# SCH_2023_-_Masters_Project_2023-11-29.net
KiCad netlist of a schematic drawn in EasyEDA
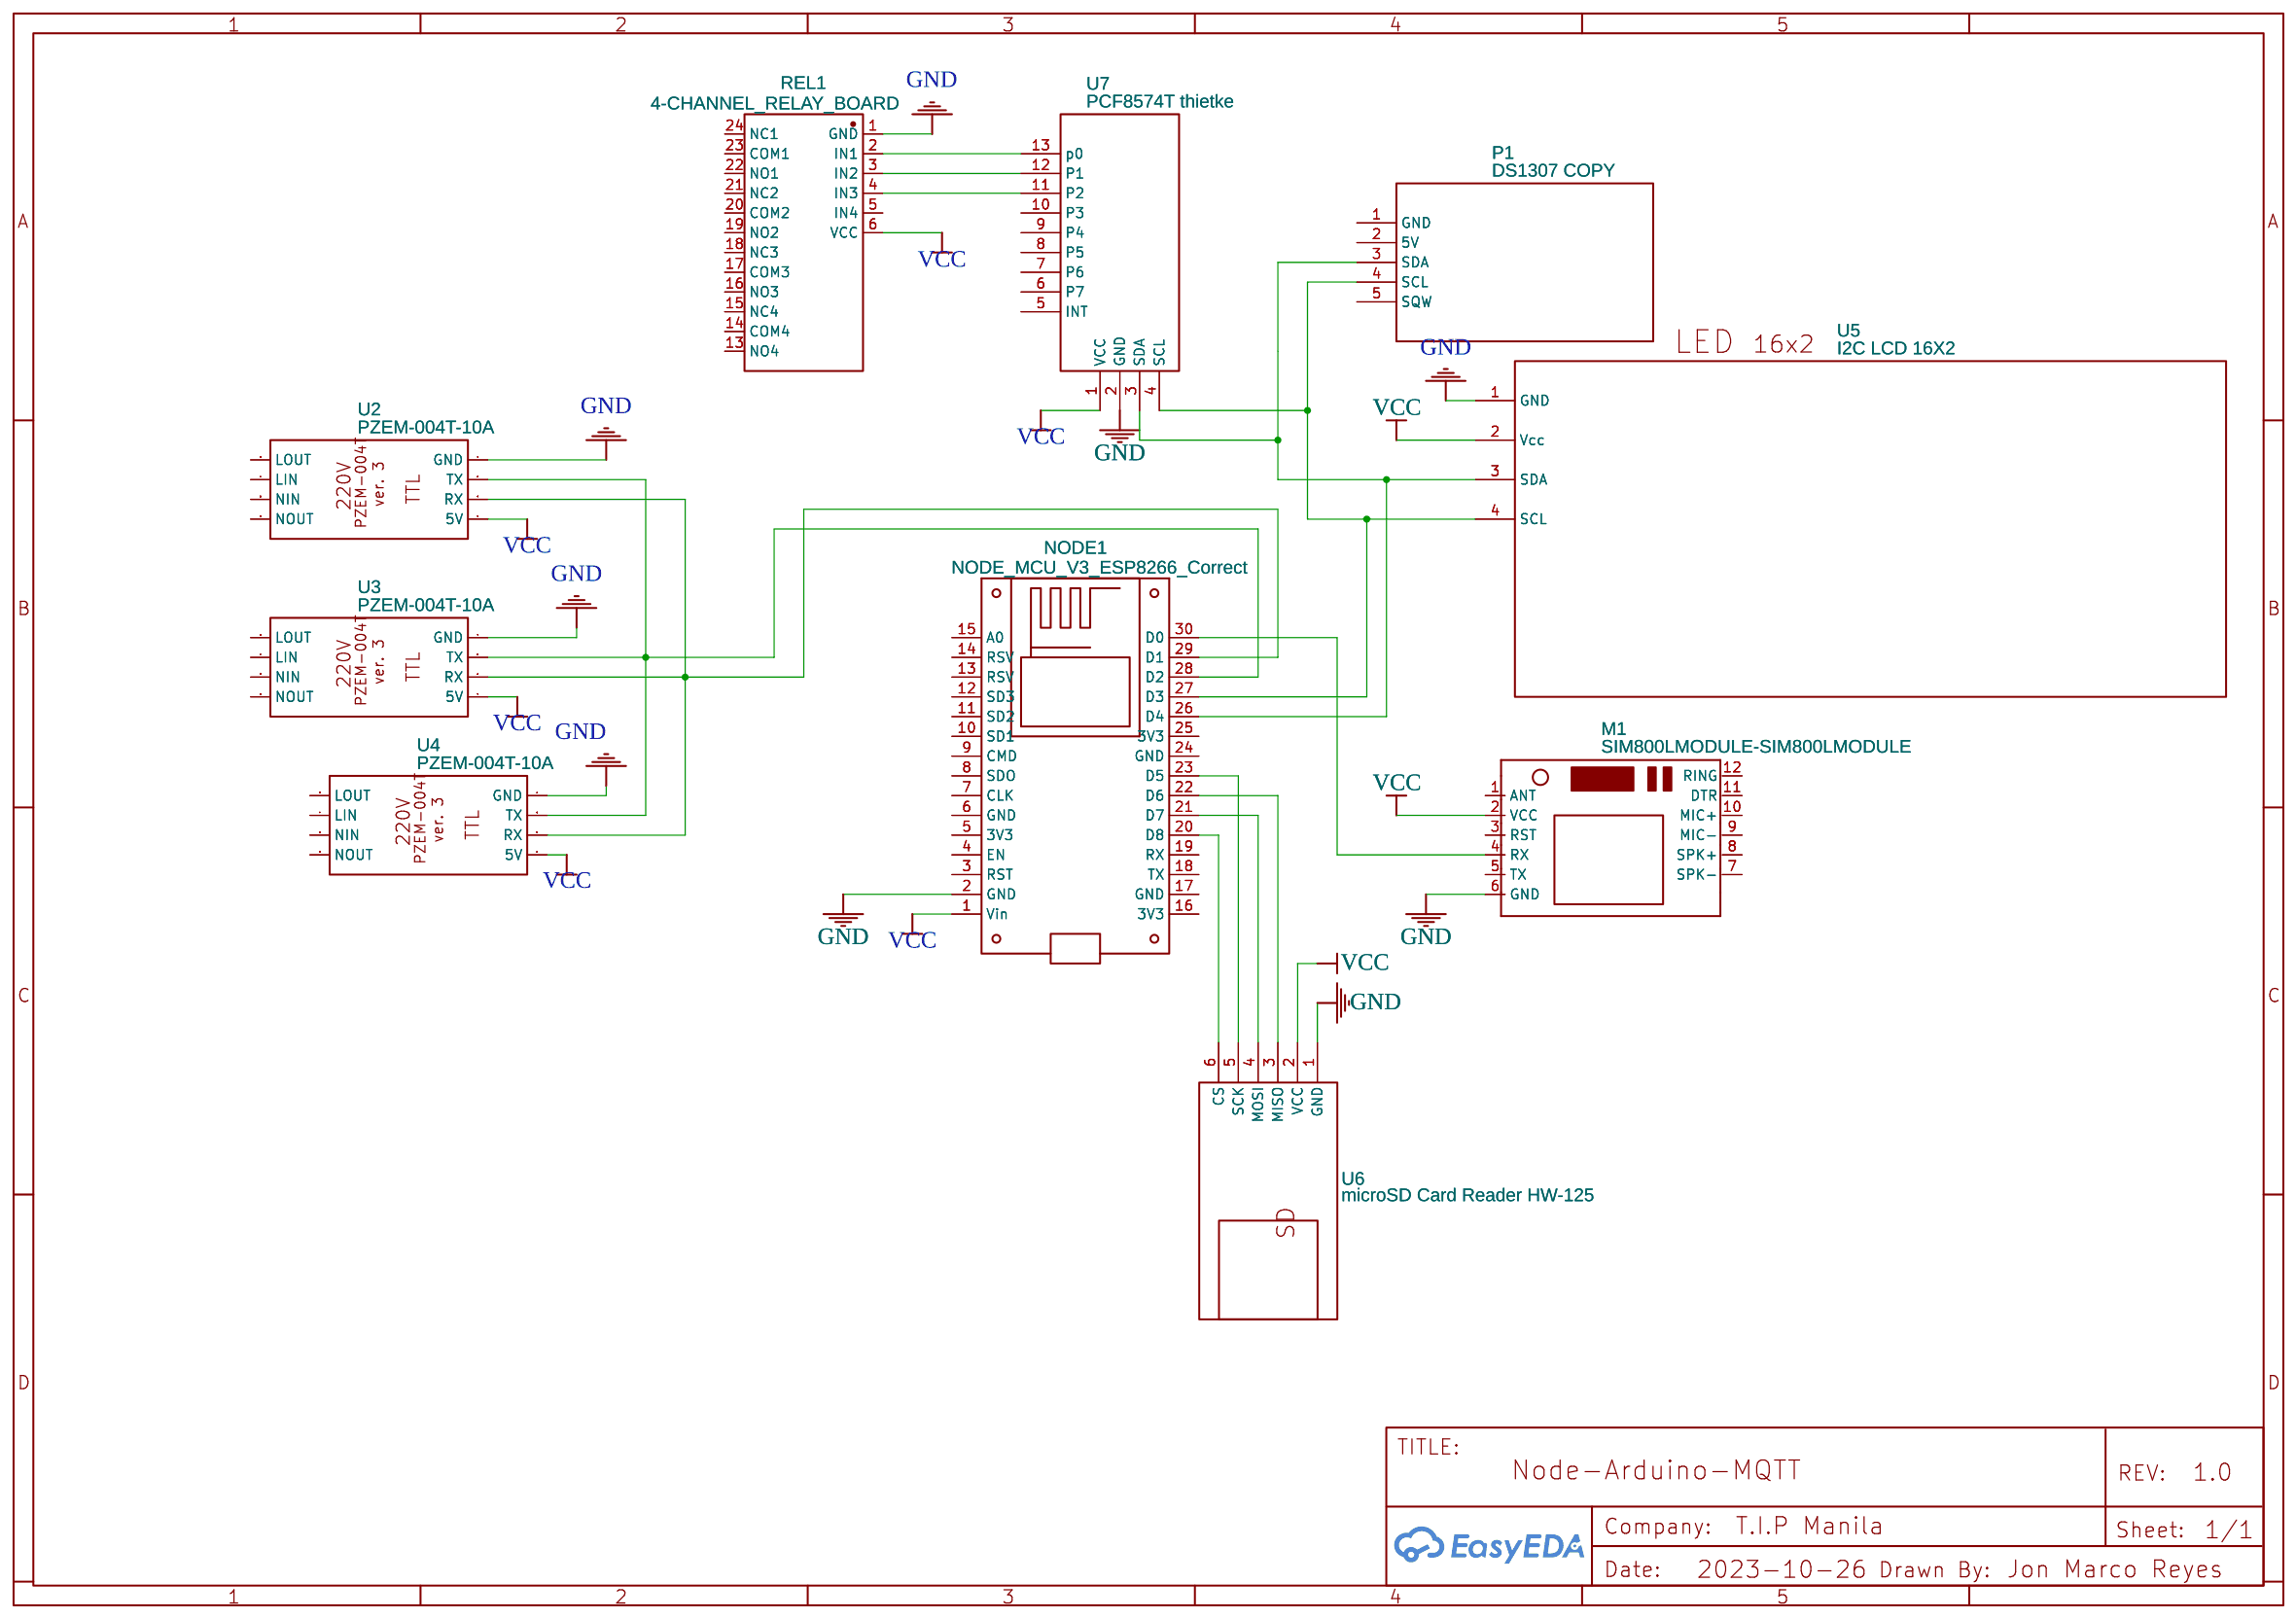
[diagram p0: schematic sheet]

(export (version "E")
  (design (tool "Eeschema 10.0.6"))
  (components
    (comp (ref "M1")
      (value "SIM800LMODULE-SIM800LMODULE")
      (libsource (lib "") (part "SIM800LMODULE-SIM800LMODULE"))
    )
    (comp (ref "NODE1")
      (value "NODE_MCU_V3_ESP8266_Correct")
      (libsource (lib "") (part "NODE_MCU_V3_ESP8266_Correct"))
    )
    (comp (ref "P1") (value "DS1307 COPY") (libsource (lib "") (part "DS1307 COPY")))
    (comp (ref "REL1") (value "4-CHANNEL_RELAY_BOARD") (libsource (lib "") (part "4-CHANNEL_RELAY_BOARD")))
    (comp (ref "U2") (value "PZEM-004T-10A") (libsource (lib "") (part "PZEM-004T-10A")))
    (comp (ref "U3") (value "PZEM-004T-10A") (libsource (lib "") (part "PZEM-004T-10A")))
    (comp (ref "U4") (value "PZEM-004T-10A") (libsource (lib "") (part "PZEM-004T-10A")))
    (comp (ref "U5") (value "I2C LCD 16X2") (libsource (lib "") (part "I2C LCD 16X2")))
    (comp (ref "U6")
      (value "microSD Card Reader HW-125")
      (libsource (lib "") (part "microSD Card Reader HW-125"))
    )
    (comp (ref "U7") (value "PCF8574T thietke") (libsource (lib "") (part "PCF8574T thietke")))
  )
  (nets
    (net (code "1") (name "GND") (class "Default")
      (node (ref "M1") (pin "6") (pinfunction "GND_6") (pintype "output"))
      (node (ref "NODE1") (pin "2") (pinfunction "GND_2") (pintype "unspecified"))
      (node (ref "REL1") (pin "1") (pinfunction "GND_1") (pintype "unspecified"))
      (node (ref "U2") (pin "4") (pinfunction "GND_4") (pintype "unspecified"))
      (node (ref "U3") (pin "4") (pinfunction "GND_4") (pintype "unspecified"))
      (node (ref "U4") (pin "4") (pinfunction "GND_4") (pintype "unspecified"))
      (node (ref "U5") (pin "1") (pinfunction "GND_1") (pintype "unspecified"))
      (node (ref "U6") (pin "1") (pinfunction "GND_1") (pintype "unspecified"))
      (node (ref "U7") (pin "2") (pinfunction "GND_2") (pintype "unspecified"))
    )
    (net (code "2") (name "Net-(M1-RX)") (class "Default")
      (node (ref "M1") (pin "4") (pinfunction "RX_4") (pintype "input"))
      (node (ref "NODE1") (pin "30") (pinfunction "D0_30") (pintype "unspecified"))
    )
    (net (code "3") (name "Net-(NODE1-D1)") (class "Default")
      (node (ref "NODE1") (pin "29") (pinfunction "D1_29") (pintype "unspecified"))
      (node (ref "U2") (pin "2") (pinfunction "RX_2") (pintype "unspecified"))
      (node (ref "U3") (pin "2") (pinfunction "RX_2") (pintype "unspecified"))
      (node (ref "U4") (pin "2") (pinfunction "RX_2") (pintype "unspecified"))
    )
    (net (code "4") (name "Net-(NODE1-D2)") (class "Default")
      (node (ref "NODE1") (pin "28") (pinfunction "D2_28") (pintype "unspecified"))
      (node (ref "U2") (pin "3") (pinfunction "TX_3") (pintype "unspecified"))
      (node (ref "U3") (pin "3") (pinfunction "TX_3") (pintype "unspecified"))
      (node (ref "U4") (pin "3") (pinfunction "TX_3") (pintype "unspecified"))
    )
    (net (code "5") (name "Net-(NODE1-D3)") (class "Default")
      (node (ref "NODE1") (pin "27") (pinfunction "D3_27") (pintype "unspecified"))
      (node (ref "P1") (pin "4") (pinfunction "SCL_4") (pintype "unspecified"))
      (node (ref "U5") (pin "4") (pinfunction "SCL_4") (pintype "unspecified"))
      (node (ref "U7") (pin "4") (pinfunction "SCL_4") (pintype "unspecified"))
    )
    (net (code "6") (name "Net-(NODE1-D4)") (class "Default")
      (node (ref "NODE1") (pin "26") (pinfunction "D4_26") (pintype "unspecified"))
      (node (ref "P1") (pin "3") (pinfunction "SDA_3") (pintype "unspecified"))
      (node (ref "U5") (pin "3") (pinfunction "SDA_3") (pintype "unspecified"))
      (node (ref "U7") (pin "3") (pinfunction "SDA_3") (pintype "unspecified"))
    )
    (net (code "7") (name "Net-(NODE1-D5)") (class "Default")
      (node (ref "NODE1") (pin "23") (pinfunction "D5_23") (pintype "unspecified"))
      (node (ref "U6") (pin "5") (pinfunction "SCK_5") (pintype "unspecified"))
    )
    (net (code "8") (name "Net-(NODE1-D6)") (class "Default")
      (node (ref "NODE1") (pin "22") (pinfunction "D6_22") (pintype "unspecified"))
      (node (ref "U6") (pin "3") (pinfunction "MISO_3") (pintype "unspecified"))
    )
    (net (code "9") (name "Net-(NODE1-D7)") (class "Default")
      (node (ref "NODE1") (pin "21") (pinfunction "D7_21") (pintype "unspecified"))
      (node (ref "U6") (pin "4") (pinfunction "MOSI_4") (pintype "unspecified"))
    )
    (net (code "10") (name "Net-(NODE1-D8)") (class "Default")
      (node (ref "NODE1") (pin "20") (pinfunction "D8_20") (pintype "unspecified"))
      (node (ref "U6") (pin "6") (pinfunction "CS_6") (pintype "unspecified"))
    )
    (net (code "11") (name "Net-(REL1-IN1)") (class "Default")
      (node (ref "REL1") (pin "2") (pinfunction "IN1_2") (pintype "unspecified"))
      (node (ref "U7") (pin "13") (pinfunction "p0_13") (pintype "unspecified"))
    )
    (net (code "12") (name "Net-(REL1-IN2)") (class "Default")
      (node (ref "REL1") (pin "3") (pinfunction "IN2_3") (pintype "unspecified"))
      (node (ref "U7") (pin "12") (pinfunction "P1_12") (pintype "unspecified"))
    )
    (net (code "13") (name "Net-(REL1-IN3)") (class "Default")
      (node (ref "REL1") (pin "4") (pinfunction "IN3_4") (pintype "unspecified"))
      (node (ref "U7") (pin "11") (pinfunction "P2_11") (pintype "unspecified"))
    )
    (net (code "14") (name "VCC") (class "Default")
      (node (ref "M1") (pin "2") (pinfunction "VCC_2") (pintype "input"))
      (node (ref "NODE1") (pin "1") (pinfunction "Vin_1") (pintype "unspecified"))
      (node (ref "REL1") (pin "6") (pinfunction "VCC_6") (pintype "unspecified"))
      (node (ref "U2") (pin "1") (pinfunction "5V_1") (pintype "unspecified"))
      (node (ref "U3") (pin "1") (pinfunction "5V_1") (pintype "unspecified"))
      (node (ref "U4") (pin "1") (pinfunction "5V_1") (pintype "unspecified"))
      (node (ref "U5") (pin "2") (pinfunction "Vcc_2") (pintype "unspecified"))
      (node (ref "U6") (pin "2") (pinfunction "VCC_2") (pintype "unspecified"))
      (node (ref "U7") (pin "1") (pinfunction "VCC_1") (pintype "unspecified"))
    )
    (net (code "15") (name "unconnected-(M1-ANT-Pad1)") (class "Default")
      (node (ref "M1") (pin "1") (pinfunction "ANT_1") (pintype "output"))
    )
    (net (code "16") (name "unconnected-(M1-DTR-Pad11)") (class "Default")
      (node (ref "M1") (pin "11") (pinfunction "DTR_11") (pintype "output"))
    )
    (net (code "17") (name "unconnected-(M1-MIC+-Pad10)") (class "Default")
      (node (ref "M1") (pin "10") (pinfunction "MIC+_10") (pintype "input"))
    )
    (net (code "18") (name "unconnected-(M1-MIC--Pad9)") (class "Default")
      (node (ref "M1") (pin "9") (pinfunction "MIC-_9") (pintype "input"))
    )
    (net (code "19") (name "unconnected-(M1-RING-Pad12)") (class "Default")
      (node (ref "M1") (pin "12") (pinfunction "RING_12") (pintype "output"))
    )
    (net (code "20") (name "unconnected-(M1-RST-Pad3)") (class "Default")
      (node (ref "M1") (pin "3") (pinfunction "RST_3") (pintype "input"))
    )
    (net (code "21") (name "unconnected-(M1-SPK+-Pad8)") (class "Default")
      (node (ref "M1") (pin "8") (pinfunction "SPK+_8") (pintype "output"))
    )
    (net (code "22") (name "unconnected-(M1-SPK--Pad7)") (class "Default")
      (node (ref "M1") (pin "7") (pinfunction "SPK-_7") (pintype "output"))
    )
    (net (code "23") (name "unconnected-(M1-TX-Pad5)") (class "Default")
      (node (ref "M1") (pin "5") (pinfunction "TX_5") (pintype "output"))
    )
    (net (code "24") (name "unconnected-(NODE1-3V3-Pad5)") (class "Default")
      (node (ref "NODE1") (pin "5") (pinfunction "3V3_5") (pintype "unspecified"))
    )
    (net (code "25") (name "unconnected-(NODE1-3V3-Pad16)") (class "Default")
      (node (ref "NODE1") (pin "16") (pinfunction "3V3_16") (pintype "unspecified"))
    )
    (net (code "26") (name "unconnected-(NODE1-3V3-Pad25)") (class "Default")
      (node (ref "NODE1") (pin "25") (pinfunction "3V3_25") (pintype "unspecified"))
    )
    (net (code "27") (name "unconnected-(NODE1-A0-Pad15)") (class "Default")
      (node (ref "NODE1") (pin "15") (pinfunction "A0_15") (pintype "unspecified"))
    )
    (net (code "28") (name "unconnected-(NODE1-CLK-Pad7)") (class "Default")
      (node (ref "NODE1") (pin "7") (pinfunction "CLK_7") (pintype "unspecified"))
    )
    (net (code "29") (name "unconnected-(NODE1-CMD-Pad9)") (class "Default")
      (node (ref "NODE1") (pin "9") (pinfunction "CMD_9") (pintype "unspecified"))
    )
    (net (code "30") (name "unconnected-(NODE1-EN-Pad4)") (class "Default")
      (node (ref "NODE1") (pin "4") (pinfunction "EN_4") (pintype "unspecified"))
    )
    (net (code "31") (name "unconnected-(NODE1-GND-Pad6)") (class "Default")
      (node (ref "NODE1") (pin "6") (pinfunction "GND_6") (pintype "unspecified"))
    )
    (net (code "32") (name "unconnected-(NODE1-GND-Pad17)") (class "Default")
      (node (ref "NODE1") (pin "17") (pinfunction "GND_17") (pintype "unspecified"))
    )
    (net (code "33") (name "unconnected-(NODE1-GND-Pad24)") (class "Default")
      (node (ref "NODE1") (pin "24") (pinfunction "GND_24") (pintype "unspecified"))
    )
    (net (code "34") (name "unconnected-(NODE1-RST-Pad3)") (class "Default")
      (node (ref "NODE1") (pin "3") (pinfunction "RST_3") (pintype "unspecified"))
    )
    (net (code "35") (name "unconnected-(NODE1-RSV-Pad13)") (class "Default")
      (node (ref "NODE1") (pin "13") (pinfunction "RSV_13") (pintype "unspecified"))
    )
    (net (code "36") (name "unconnected-(NODE1-RSV-Pad14)") (class "Default")
      (node (ref "NODE1") (pin "14") (pinfunction "RSV_14") (pintype "unspecified"))
    )
    (net (code "37") (name "unconnected-(NODE1-RX-Pad19)") (class "Default")
      (node (ref "NODE1") (pin "19") (pinfunction "RX_19") (pintype "unspecified"))
    )
    (net (code "38") (name "unconnected-(NODE1-SD1-Pad10)") (class "Default")
      (node (ref "NODE1") (pin "10") (pinfunction "SD1_10") (pintype "unspecified"))
    )
    (net (code "39") (name "unconnected-(NODE1-SD2-Pad11)") (class "Default")
      (node (ref "NODE1") (pin "11") (pinfunction "SD2_11") (pintype "unspecified"))
    )
    (net (code "40") (name "unconnected-(NODE1-SD3-Pad12)") (class "Default")
      (node (ref "NODE1") (pin "12") (pinfunction "SD3_12") (pintype "unspecified"))
    )
    (net (code "41") (name "unconnected-(NODE1-SDO-Pad8)") (class "Default")
      (node (ref "NODE1") (pin "8") (pinfunction "SDO_8") (pintype "unspecified"))
    )
    (net (code "42") (name "unconnected-(NODE1-TX-Pad18)") (class "Default")
      (node (ref "NODE1") (pin "18") (pinfunction "TX_18") (pintype "unspecified"))
    )
    (net (code "43") (name "unconnected-(P1-5V-Pad2)") (class "Default")
      (node (ref "P1") (pin "2") (pinfunction "5V_2") (pintype "unspecified"))
    )
    (net (code "44") (name "unconnected-(P1-GND-Pad1)") (class "Default")
      (node (ref "P1") (pin "1") (pinfunction "GND_1") (pintype "unspecified"))
    )
    (net (code "45") (name "unconnected-(P1-SQW-Pad5)") (class "Default")
      (node (ref "P1") (pin "5") (pinfunction "SQW_5") (pintype "unspecified"))
    )
    (net (code "46") (name "unconnected-(REL1-COM1-Pad23)") (class "Default")
      (node (ref "REL1") (pin "23") (pinfunction "COM1_23") (pintype "unspecified"))
    )
    (net (code "47") (name "unconnected-(REL1-COM2-Pad20)") (class "Default")
      (node (ref "REL1") (pin "20") (pinfunction "COM2_20") (pintype "unspecified"))
    )
    (net (code "48") (name "unconnected-(REL1-COM3-Pad17)") (class "Default")
      (node (ref "REL1") (pin "17") (pinfunction "COM3_17") (pintype "unspecified"))
    )
    (net (code "49") (name "unconnected-(REL1-COM4-Pad14)") (class "Default")
      (node (ref "REL1") (pin "14") (pinfunction "COM4_14") (pintype "unspecified"))
    )
    (net (code "50") (name "unconnected-(REL1-IN4-Pad5)") (class "Default")
      (node (ref "REL1") (pin "5") (pinfunction "IN4_5") (pintype "unspecified"))
    )
    (net (code "51") (name "unconnected-(REL1-NC1-Pad24)") (class "Default")
      (node (ref "REL1") (pin "24") (pinfunction "NC1_24") (pintype "unspecified"))
    )
    (net (code "52") (name "unconnected-(REL1-NC2-Pad21)") (class "Default")
      (node (ref "REL1") (pin "21") (pinfunction "NC2_21") (pintype "unspecified"))
    )
    (net (code "53") (name "unconnected-(REL1-NC3-Pad18)") (class "Default")
      (node (ref "REL1") (pin "18") (pinfunction "NC3_18") (pintype "unspecified"))
    )
    (net (code "54") (name "unconnected-(REL1-NC4-Pad15)") (class "Default")
      (node (ref "REL1") (pin "15") (pinfunction "NC4_15") (pintype "unspecified"))
    )
    (net (code "55") (name "unconnected-(REL1-NO1-Pad22)") (class "Default")
      (node (ref "REL1") (pin "22") (pinfunction "NO1_22") (pintype "unspecified"))
    )
    (net (code "56") (name "unconnected-(REL1-NO2-Pad19)") (class "Default")
      (node (ref "REL1") (pin "19") (pinfunction "NO2_19") (pintype "unspecified"))
    )
    (net (code "57") (name "unconnected-(REL1-NO3-Pad16)") (class "Default")
      (node (ref "REL1") (pin "16") (pinfunction "NO3_16") (pintype "unspecified"))
    )
    (net (code "58") (name "unconnected-(REL1-NO4-Pad13)") (class "Default")
      (node (ref "REL1") (pin "13") (pinfunction "NO4_13") (pintype "unspecified"))
    )
    (net (code "59") (name "unconnected-(U2-LIN-Pad7)") (class "Default")
      (node (ref "U2") (pin "7") (pinfunction "LIN_7") (pintype "unspecified"))
    )
    (net (code "60") (name "unconnected-(U2-LOUT-Pad8)") (class "Default")
      (node (ref "U2") (pin "8") (pinfunction "LOUT_8") (pintype "unspecified"))
    )
    (net (code "61") (name "unconnected-(U2-NIN-Pad6)") (class "Default")
      (node (ref "U2") (pin "6") (pinfunction "NIN_6") (pintype "unspecified"))
    )
    (net (code "62") (name "unconnected-(U2-NOUT-Pad5)") (class "Default")
      (node (ref "U2") (pin "5") (pinfunction "NOUT_5") (pintype "unspecified"))
    )
    (net (code "63") (name "unconnected-(U3-LIN-Pad7)") (class "Default")
      (node (ref "U3") (pin "7") (pinfunction "LIN_7") (pintype "unspecified"))
    )
    (net (code "64") (name "unconnected-(U3-LOUT-Pad8)") (class "Default")
      (node (ref "U3") (pin "8") (pinfunction "LOUT_8") (pintype "unspecified"))
    )
    (net (code "65") (name "unconnected-(U3-NIN-Pad6)") (class "Default")
      (node (ref "U3") (pin "6") (pinfunction "NIN_6") (pintype "unspecified"))
    )
    (net (code "66") (name "unconnected-(U3-NOUT-Pad5)") (class "Default")
      (node (ref "U3") (pin "5") (pinfunction "NOUT_5") (pintype "unspecified"))
    )
    (net (code "67") (name "unconnected-(U4-LIN-Pad7)") (class "Default")
      (node (ref "U4") (pin "7") (pinfunction "LIN_7") (pintype "unspecified"))
    )
    (net (code "68") (name "unconnected-(U4-LOUT-Pad8)") (class "Default")
      (node (ref "U4") (pin "8") (pinfunction "LOUT_8") (pintype "unspecified"))
    )
    (net (code "69") (name "unconnected-(U4-NIN-Pad6)") (class "Default")
      (node (ref "U4") (pin "6") (pinfunction "NIN_6") (pintype "unspecified"))
    )
    (net (code "70") (name "unconnected-(U4-NOUT-Pad5)") (class "Default")
      (node (ref "U4") (pin "5") (pinfunction "NOUT_5") (pintype "unspecified"))
    )
    (net (code "71") (name "unconnected-(U7-INT-Pad5)") (class "Default")
      (node (ref "U7") (pin "5") (pinfunction "INT_5") (pintype "unspecified"))
    )
    (net (code "72") (name "unconnected-(U7-P3-Pad10)") (class "Default")
      (node (ref "U7") (pin "10") (pinfunction "P3_10") (pintype "unspecified"))
    )
    (net (code "73") (name "unconnected-(U7-P4-Pad9)") (class "Default")
      (node (ref "U7") (pin "9") (pinfunction "P4_9") (pintype "unspecified"))
    )
    (net (code "74") (name "unconnected-(U7-P5-Pad8)") (class "Default")
      (node (ref "U7") (pin "8") (pinfunction "P5_8") (pintype "unspecified"))
    )
    (net (code "75") (name "unconnected-(U7-P6-Pad7)") (class "Default")
      (node (ref "U7") (pin "7") (pinfunction "P6_7") (pintype "unspecified"))
    )
    (net (code "76") (name "unconnected-(U7-P7-Pad6)") (class "Default")
      (node (ref "U7") (pin "6") (pinfunction "P7_6") (pintype "unspecified"))
    )
  )
)
